# ShieldEsquematico.net
KiCad netlist of a schematic drawn in EAGLE
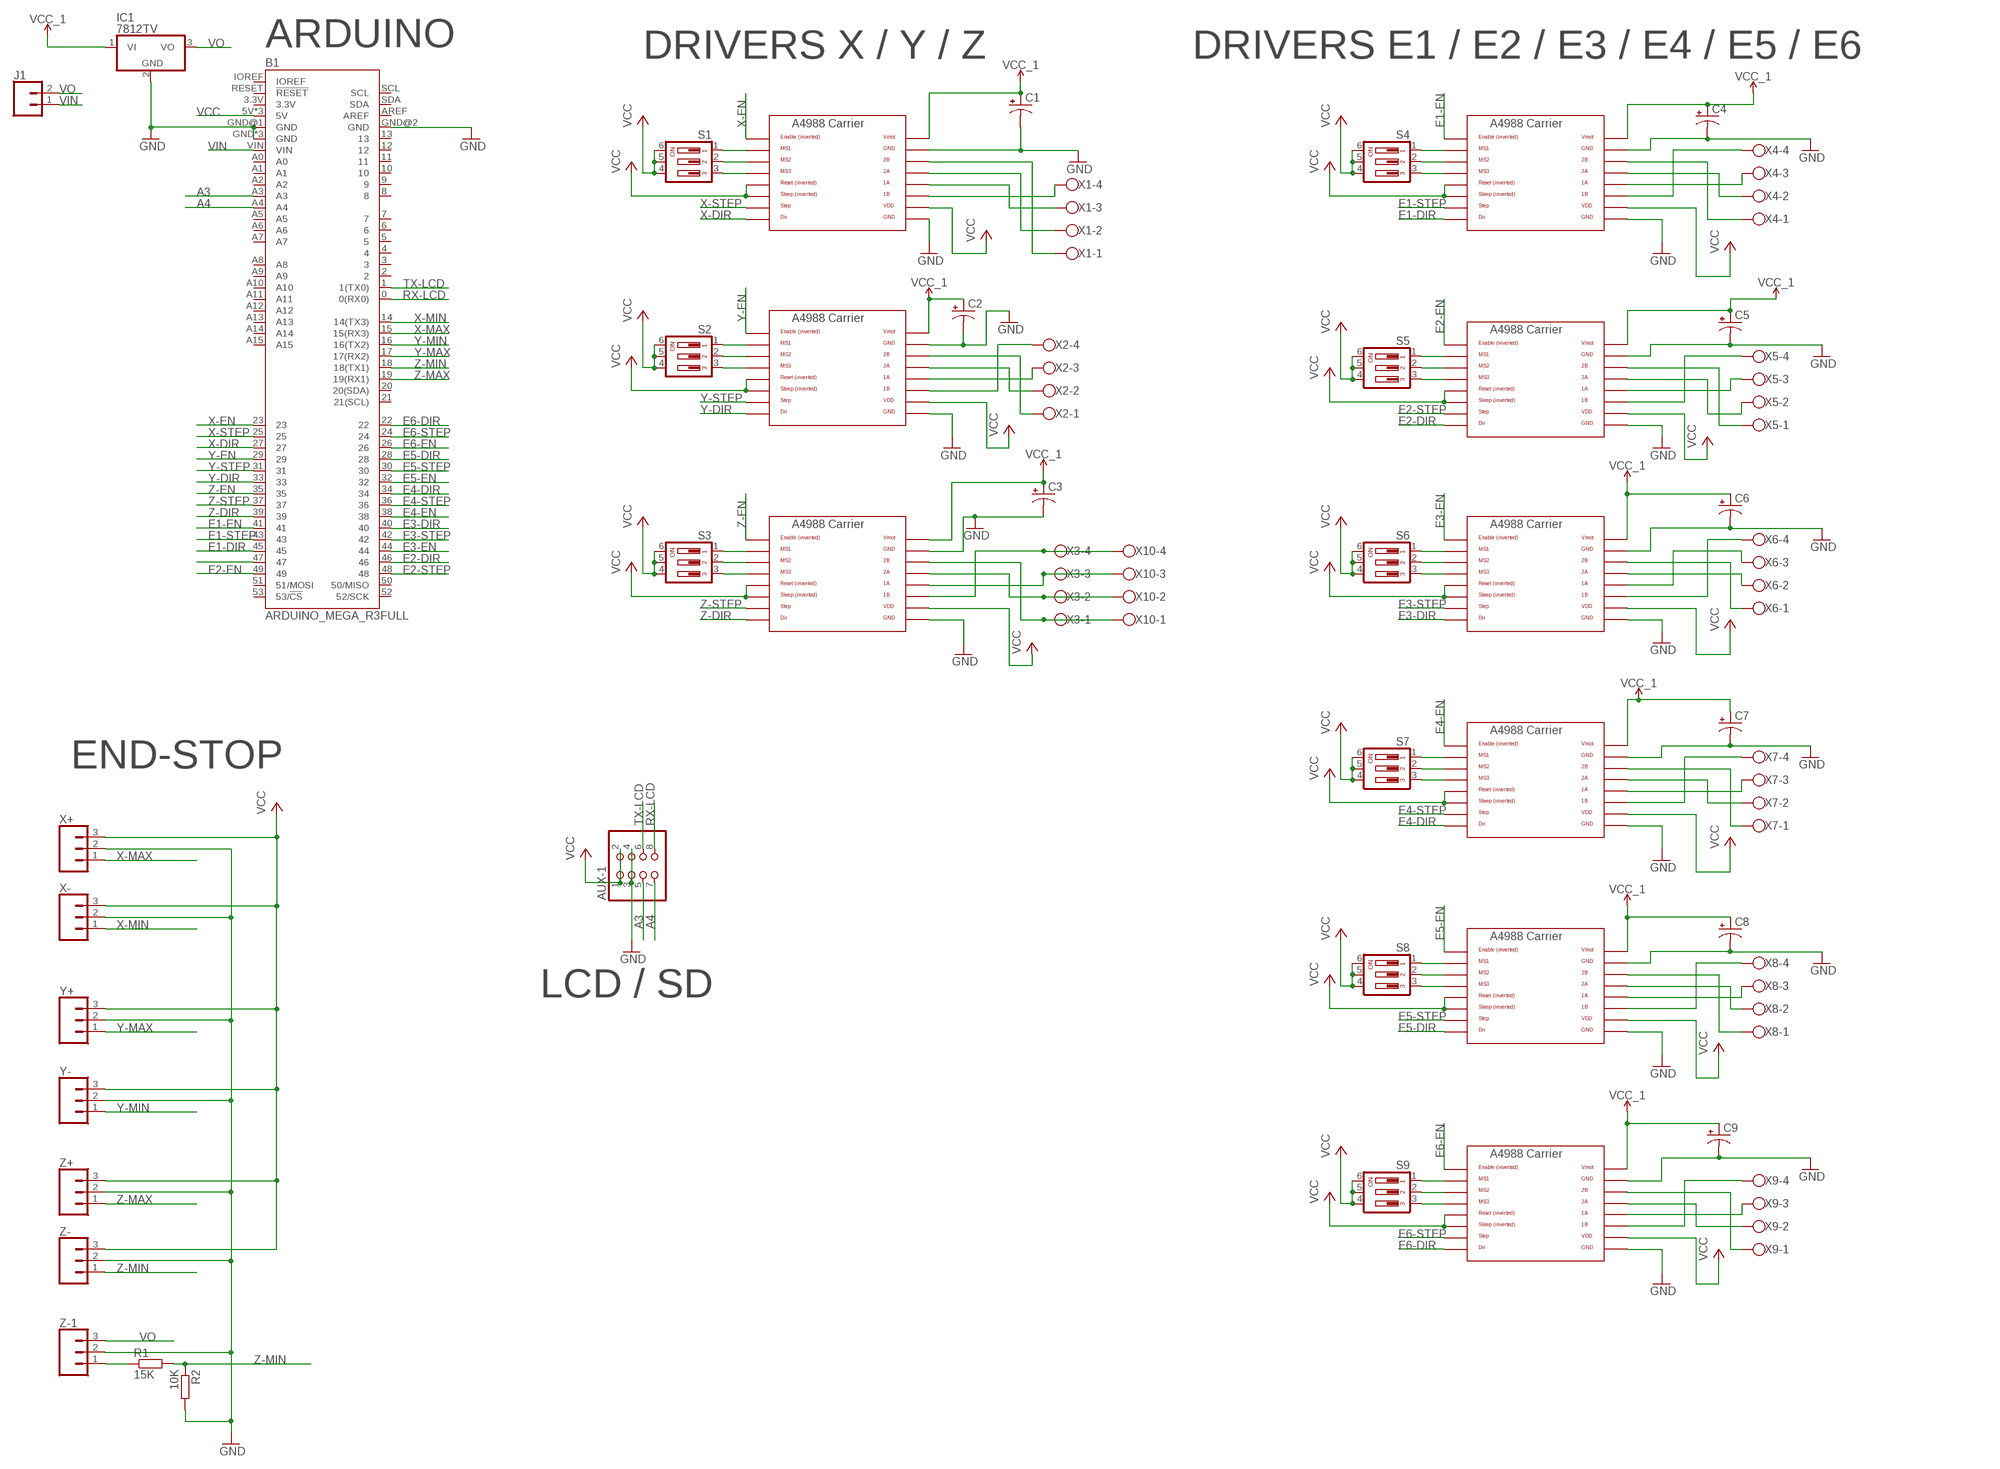
[diagram p0: schematic, sheet 1]

(export (version "E")
  (design (tool "Eeschema 10.0.6"))
  (components
    (comp (ref "AUX-1")
      (value "PINHD-2X4")
      (footprint "eagle-import:2X04")
      (libsource (lib "eagle-import") (part "PINHD-2X4"))
    )
    (comp (ref "B1")
      (value "ARDUINO_MEGA_R3FULL")
      (footprint "eagle-import:ARDUINO_MEGA_NO_SILK")
      (libsource (lib "eagle-import") (part "ARDUINO_MEGA_R3FULL"))
    )
    (comp (ref "C1")
      (value "CPOL-USE5-8.5")
      (footprint "eagle-import:E5-8,5")
      (libsource (lib "eagle-import") (part "CPOL-USE5-8.5"))
    )
    (comp (ref "C2")
      (value "CPOL-USE5-8.5")
      (footprint "eagle-import:E5-8,5")
      (libsource (lib "eagle-import") (part "CPOL-USE5-8.5"))
    )
    (comp (ref "C3")
      (value "CPOL-USE5-8.5")
      (footprint "eagle-import:E5-8,5")
      (libsource (lib "eagle-import") (part "CPOL-USE5-8.5"))
    )
    (comp (ref "C4")
      (value "CPOL-USE5-8.5")
      (footprint "eagle-import:E5-8,5")
      (libsource (lib "eagle-import") (part "CPOL-USE5-8.5"))
    )
    (comp (ref "C5")
      (value "CPOL-USE5-8.5")
      (footprint "eagle-import:E5-8,5")
      (libsource (lib "eagle-import") (part "CPOL-USE5-8.5"))
    )
    (comp (ref "C6")
      (value "CPOL-USE5-8.5")
      (footprint "eagle-import:E5-8,5")
      (libsource (lib "eagle-import") (part "CPOL-USE5-8.5"))
    )
    (comp (ref "C7")
      (value "CPOL-USE5-8.5")
      (footprint "eagle-import:E5-8,5")
      (libsource (lib "eagle-import") (part "CPOL-USE5-8.5"))
    )
    (comp (ref "C8")
      (value "CPOL-USE5-8.5")
      (footprint "eagle-import:E5-8,5")
      (libsource (lib "eagle-import") (part "CPOL-USE5-8.5"))
    )
    (comp (ref "C9")
      (value "CPOL-USE5-8.5")
      (footprint "eagle-import:E5-8,5")
      (libsource (lib "eagle-import") (part "CPOL-USE5-8.5"))
    )
    (comp (ref "IC1")
      (value "7812TV")
      (footprint "eagle-import:TO220V")
      (libsource (lib "eagle-import") (part "78TV12"))
    )
    (comp (ref "J1")
      (value "CONN_02")
      (footprint "eagle-import:1X02")
      (libsource (lib "eagle-import") (part "CONN_02"))
    )
    (comp (ref "R1")
      (value "15K")
      (footprint "eagle-import:0207_10")
      (libsource (lib "eagle-import") (part "R-EU_0207/10"))
    )
    (comp (ref "R2")
      (value "10K")
      (footprint "eagle-import:0207_10")
      (libsource (lib "eagle-import") (part "R-EU_0207/10"))
    )
    (comp (ref "S1")
      (value "DIP03YL")
      (footprint "eagle-import:DIP03YL")
      (libsource (lib "eagle-import") (part "DIP03YL"))
    )
    (comp (ref "S2")
      (value "DIP03YL")
      (footprint "eagle-import:DIP03YL")
      (libsource (lib "eagle-import") (part "DIP03YL"))
    )
    (comp (ref "S3")
      (value "DIP03YL")
      (footprint "eagle-import:DIP03YL")
      (libsource (lib "eagle-import") (part "DIP03YL"))
    )
    (comp (ref "S4")
      (value "DIP03YL")
      (footprint "eagle-import:DIP03YL")
      (libsource (lib "eagle-import") (part "DIP03YL"))
    )
    (comp (ref "S5")
      (value "DIP03YL")
      (footprint "eagle-import:DIP03YL")
      (libsource (lib "eagle-import") (part "DIP03YL"))
    )
    (comp (ref "S6")
      (value "DIP03YL")
      (footprint "eagle-import:DIP03YL")
      (libsource (lib "eagle-import") (part "DIP03YL"))
    )
    (comp (ref "S7")
      (value "DIP03YL")
      (footprint "eagle-import:DIP03YL")
      (libsource (lib "eagle-import") (part "DIP03YL"))
    )
    (comp (ref "S8")
      (value "DIP03YL")
      (footprint "eagle-import:DIP03YL")
      (libsource (lib "eagle-import") (part "DIP03YL"))
    )
    (comp (ref "S9")
      (value "DIP03YL")
      (footprint "eagle-import:DIP03YL")
      (libsource (lib "eagle-import") (part "DIP03YL"))
    )
    (comp (ref "U$1")
      (value "A4988BREAKOUT")
      (footprint "eagle-import:A4988BREAKOUT")
      (libsource (lib "eagle-import") (part "A4988BREAKOUT"))
    )
    (comp (ref "U$2")
      (value "A4988BREAKOUT")
      (footprint "eagle-import:A4988BREAKOUT")
      (libsource (lib "eagle-import") (part "A4988BREAKOUT"))
    )
    (comp (ref "U$3")
      (value "A4988BREAKOUT")
      (footprint "eagle-import:A4988BREAKOUT")
      (libsource (lib "eagle-import") (part "A4988BREAKOUT"))
    )
    (comp (ref "U$4")
      (value "A4988BREAKOUT")
      (footprint "eagle-import:A4988BREAKOUT")
      (libsource (lib "eagle-import") (part "A4988BREAKOUT"))
    )
    (comp (ref "U$5")
      (value "A4988BREAKOUT")
      (footprint "eagle-import:A4988BREAKOUT")
      (libsource (lib "eagle-import") (part "A4988BREAKOUT"))
    )
    (comp (ref "U$6")
      (value "A4988BREAKOUT")
      (footprint "eagle-import:A4988BREAKOUT")
      (libsource (lib "eagle-import") (part "A4988BREAKOUT"))
    )
    (comp (ref "U$7")
      (value "A4988BREAKOUT")
      (footprint "eagle-import:A4988BREAKOUT")
      (libsource (lib "eagle-import") (part "A4988BREAKOUT"))
    )
    (comp (ref "U$8")
      (value "A4988BREAKOUT")
      (footprint "eagle-import:A4988BREAKOUT")
      (libsource (lib "eagle-import") (part "A4988BREAKOUT"))
    )
    (comp (ref "U$9")
      (value "A4988BREAKOUT")
      (footprint "eagle-import:A4988BREAKOUT")
      (libsource (lib "eagle-import") (part "A4988BREAKOUT"))
    )
    (comp (ref "X+")
      (value "CONN_03SCREW_LOCK")
      (footprint "eagle-import:SCREWTERMINAL-3.5MM-3_LOCK.007S")
      (libsource (lib "eagle-import") (part "CONN_03SCREW_LOCK"))
    )
    (comp (ref "X-")
      (value "CONN_03SCREW_LOCK")
      (footprint "eagle-import:SCREWTERMINAL-3.5MM-3_LOCK.007S")
      (libsource (lib "eagle-import") (part "CONN_03SCREW_LOCK"))
    )
    (comp (ref "X1")
      (value "W237-4")
      (footprint "eagle-import:W237-4")
      (libsource (lib "eagle-import") (part "W237-4"))
    )
    (comp (ref "X2")
      (value "W237-4")
      (footprint "eagle-import:W237-4")
      (libsource (lib "eagle-import") (part "W237-4"))
    )
    (comp (ref "X3")
      (value "W237-4")
      (footprint "eagle-import:W237-4")
      (libsource (lib "eagle-import") (part "W237-4"))
    )
    (comp (ref "X4")
      (value "W237-4")
      (footprint "eagle-import:W237-4")
      (libsource (lib "eagle-import") (part "W237-4"))
    )
    (comp (ref "X5")
      (value "W237-4")
      (footprint "eagle-import:W237-4")
      (libsource (lib "eagle-import") (part "W237-4"))
    )
    (comp (ref "X6")
      (value "W237-4")
      (footprint "eagle-import:W237-4")
      (libsource (lib "eagle-import") (part "W237-4"))
    )
    (comp (ref "X7")
      (value "W237-4")
      (footprint "eagle-import:W237-4")
      (libsource (lib "eagle-import") (part "W237-4"))
    )
    (comp (ref "X8")
      (value "W237-4")
      (footprint "eagle-import:W237-4")
      (libsource (lib "eagle-import") (part "W237-4"))
    )
    (comp (ref "X9")
      (value "W237-4")
      (footprint "eagle-import:W237-4")
      (libsource (lib "eagle-import") (part "W237-4"))
    )
    (comp (ref "X10")
      (value "W237-4")
      (footprint "eagle-import:W237-4")
      (libsource (lib "eagle-import") (part "W237-4"))
    )
    (comp (ref "Y+")
      (value "CONN_03SCREW_LOCK")
      (footprint "eagle-import:SCREWTERMINAL-3.5MM-3_LOCK.007S")
      (libsource (lib "eagle-import") (part "CONN_03SCREW_LOCK"))
    )
    (comp (ref "Y-")
      (value "CONN_03SCREW_LOCK")
      (footprint "eagle-import:SCREWTERMINAL-3.5MM-3_LOCK.007S")
      (libsource (lib "eagle-import") (part "CONN_03SCREW_LOCK"))
    )
    (comp (ref "Z+")
      (value "CONN_03SCREW_LOCK")
      (footprint "eagle-import:SCREWTERMINAL-3.5MM-3_LOCK.007S")
      (libsource (lib "eagle-import") (part "CONN_03SCREW_LOCK"))
    )
    (comp (ref "Z-")
      (value "CONN_03SCREW_LOCK")
      (footprint "eagle-import:SCREWTERMINAL-3.5MM-3_LOCK.007S")
      (libsource (lib "eagle-import") (part "CONN_03SCREW_LOCK"))
    )
    (comp (ref "Z-1")
      (value "CONN_03SCREW_LOCK")
      (footprint "eagle-import:SCREWTERMINAL-3.5MM-3_LOCK.007S")
      (libsource (lib "eagle-import") (part "CONN_03SCREW_LOCK"))
    )
  )
  (nets
    (net (code "1") (name "/A3") (class "Default")
      (node (ref "AUX-1") (pin "5") (pinfunction "5_5") (pintype "passive"))
      (node (ref "B1") (pin "A3") (pinfunction "A3_A3") (pintype "bidirectional"))
    )
    (net (code "2") (name "/A4") (class "Default")
      (node (ref "AUX-1") (pin "7") (pinfunction "7_7") (pintype "passive"))
      (node (ref "B1") (pin "A4") (pinfunction "A4_A4") (pintype "bidirectional"))
    )
    (net (code "3") (name "/E1-DIR") (class "Default")
      (node (ref "B1") (pin "45") (pinfunction "45_45") (pintype "bidirectional"))
      (node (ref "U$4") (pin "DIR") (pinfunction "DIR_DIR") (pintype "input"))
    )
    (net (code "4") (name "/E1-EN") (class "Default")
      (node (ref "B1") (pin "41") (pinfunction "41_41") (pintype "bidirectional"))
      (node (ref "U$4") (pin "EN") (pinfunction "EN_EN") (pintype "input"))
    )
    (net (code "5") (name "/E1-STEP") (class "Default")
      (node (ref "B1") (pin "43") (pinfunction "43_43") (pintype "bidirectional"))
      (node (ref "U$4") (pin "STEP") (pinfunction "STEP_STEP") (pintype "input"))
    )
    (net (code "6") (name "/E2-DIR") (class "Default")
      (node (ref "B1") (pin "46") (pinfunction "46_46") (pintype "bidirectional"))
      (node (ref "U$5") (pin "DIR") (pinfunction "DIR_DIR") (pintype "input"))
    )
    (net (code "7") (name "/E2-EN") (class "Default")
      (node (ref "B1") (pin "49") (pinfunction "49_49") (pintype "bidirectional"))
      (node (ref "U$5") (pin "EN") (pinfunction "EN_EN") (pintype "input"))
    )
    (net (code "8") (name "/E2-STEP") (class "Default")
      (node (ref "B1") (pin "48") (pinfunction "48_48") (pintype "bidirectional"))
      (node (ref "U$5") (pin "STEP") (pinfunction "STEP_STEP") (pintype "input"))
    )
    (net (code "9") (name "/E3-DIR") (class "Default")
      (node (ref "B1") (pin "40") (pinfunction "40_40") (pintype "bidirectional"))
      (node (ref "U$6") (pin "DIR") (pinfunction "DIR_DIR") (pintype "input"))
    )
    (net (code "10") (name "/E3-EN") (class "Default")
      (node (ref "B1") (pin "44") (pinfunction "44_44") (pintype "bidirectional"))
      (node (ref "U$6") (pin "EN") (pinfunction "EN_EN") (pintype "input"))
    )
    (net (code "11") (name "/E3-STEP") (class "Default")
      (node (ref "B1") (pin "42") (pinfunction "42_42") (pintype "bidirectional"))
      (node (ref "U$6") (pin "STEP") (pinfunction "STEP_STEP") (pintype "input"))
    )
    (net (code "12") (name "/E4-DIR") (class "Default")
      (node (ref "B1") (pin "34") (pinfunction "34_34") (pintype "bidirectional"))
      (node (ref "U$7") (pin "DIR") (pinfunction "DIR_DIR") (pintype "input"))
    )
    (net (code "13") (name "/E4-EN") (class "Default")
      (node (ref "B1") (pin "38") (pinfunction "38_38") (pintype "bidirectional"))
      (node (ref "U$7") (pin "EN") (pinfunction "EN_EN") (pintype "input"))
    )
    (net (code "14") (name "/E4-STEP") (class "Default")
      (node (ref "B1") (pin "36") (pinfunction "36_36") (pintype "bidirectional"))
      (node (ref "U$7") (pin "STEP") (pinfunction "STEP_STEP") (pintype "input"))
    )
    (net (code "15") (name "/E5-DIR") (class "Default")
      (node (ref "B1") (pin "28") (pinfunction "28_28") (pintype "bidirectional"))
      (node (ref "U$8") (pin "DIR") (pinfunction "DIR_DIR") (pintype "input"))
    )
    (net (code "16") (name "/E5-EN") (class "Default")
      (node (ref "B1") (pin "32") (pinfunction "32_32") (pintype "bidirectional"))
      (node (ref "U$8") (pin "EN") (pinfunction "EN_EN") (pintype "input"))
    )
    (net (code "17") (name "/E5-STEP") (class "Default")
      (node (ref "B1") (pin "30") (pinfunction "30_30") (pintype "bidirectional"))
      (node (ref "U$8") (pin "STEP") (pinfunction "STEP_STEP") (pintype "input"))
    )
    (net (code "18") (name "/E6-DIR") (class "Default")
      (node (ref "B1") (pin "22") (pinfunction "22_22") (pintype "bidirectional"))
      (node (ref "U$9") (pin "DIR") (pinfunction "DIR_DIR") (pintype "input"))
    )
    (net (code "19") (name "/E6-EN") (class "Default")
      (node (ref "B1") (pin "26") (pinfunction "26_26") (pintype "bidirectional"))
      (node (ref "U$9") (pin "EN") (pinfunction "EN_EN") (pintype "input"))
    )
    (net (code "20") (name "/E6-STEP") (class "Default")
      (node (ref "B1") (pin "24") (pinfunction "24_24") (pintype "bidirectional"))
      (node (ref "U$9") (pin "STEP") (pinfunction "STEP_STEP") (pintype "input"))
    )
    (net (code "21") (name "/RX-LCD") (class "Default")
      (node (ref "AUX-1") (pin "8") (pinfunction "8_8") (pintype "passive"))
      (node (ref "B1") (pin "0") (pinfunction "0(RX0)_0") (pintype "bidirectional"))
    )
    (net (code "22") (name "/TX-LCD") (class "Default")
      (node (ref "AUX-1") (pin "6") (pinfunction "6_6") (pintype "passive"))
      (node (ref "B1") (pin "1") (pinfunction "1(TX0)_1") (pintype "bidirectional"))
    )
    (net (code "23") (name "/VIN") (class "Default")
      (node (ref "B1") (pin "VIN") (pinfunction "VIN_VIN") (pintype "bidirectional"))
      (node (ref "J1") (pin "1") (pinfunction "1_1") (pintype "passive"))
    )
    (net (code "24") (name "/VO") (class "Default")
      (node (ref "IC1") (pin "3") (pinfunction "VO_3") (pintype "passive"))
      (node (ref "J1") (pin "2") (pinfunction "2_2") (pintype "passive"))
      (node (ref "Z-1") (pin "3") (pinfunction "3_3") (pintype "passive"))
    )
    (net (code "25") (name "/X-DIR") (class "Default")
      (node (ref "B1") (pin "27") (pinfunction "27_27") (pintype "bidirectional"))
      (node (ref "U$1") (pin "DIR") (pinfunction "DIR_DIR") (pintype "input"))
    )
    (net (code "26") (name "/X-EN") (class "Default")
      (node (ref "B1") (pin "23") (pinfunction "23_23") (pintype "bidirectional"))
      (node (ref "U$1") (pin "EN") (pinfunction "EN_EN") (pintype "input"))
    )
    (net (code "27") (name "/X-MAX") (class "Default")
      (node (ref "B1") (pin "15") (pinfunction "15(RX3)_15") (pintype "bidirectional"))
      (node (ref "X+") (pin "1") (pinfunction "1_1") (pintype "passive"))
    )
    (net (code "28") (name "/X-MIN") (class "Default")
      (node (ref "B1") (pin "14") (pinfunction "14(TX3)_14") (pintype "bidirectional"))
      (node (ref "X-") (pin "1") (pinfunction "1_1") (pintype "passive"))
    )
    (net (code "29") (name "/X-STEP") (class "Default")
      (node (ref "B1") (pin "25") (pinfunction "25_25") (pintype "bidirectional"))
      (node (ref "U$1") (pin "STEP") (pinfunction "STEP_STEP") (pintype "input"))
    )
    (net (code "30") (name "/Y-DIR") (class "Default")
      (node (ref "B1") (pin "33") (pinfunction "33_33") (pintype "bidirectional"))
      (node (ref "U$2") (pin "DIR") (pinfunction "DIR_DIR") (pintype "input"))
    )
    (net (code "31") (name "/Y-EN") (class "Default")
      (node (ref "B1") (pin "29") (pinfunction "29_29") (pintype "bidirectional"))
      (node (ref "U$2") (pin "EN") (pinfunction "EN_EN") (pintype "input"))
    )
    (net (code "32") (name "/Y-MAX") (class "Default")
      (node (ref "B1") (pin "17") (pinfunction "17(RX2)_17") (pintype "bidirectional"))
      (node (ref "Y+") (pin "1") (pinfunction "1_1") (pintype "passive"))
    )
    (net (code "33") (name "/Y-MIN") (class "Default")
      (node (ref "B1") (pin "16") (pinfunction "16(TX2)_16") (pintype "bidirectional"))
      (node (ref "Y-") (pin "1") (pinfunction "1_1") (pintype "passive"))
    )
    (net (code "34") (name "/Y-STEP") (class "Default")
      (node (ref "B1") (pin "31") (pinfunction "31_31") (pintype "bidirectional"))
      (node (ref "U$2") (pin "STEP") (pinfunction "STEP_STEP") (pintype "input"))
    )
    (net (code "35") (name "/Z-DIR") (class "Default")
      (node (ref "B1") (pin "39") (pinfunction "39_39") (pintype "bidirectional"))
      (node (ref "U$3") (pin "DIR") (pinfunction "DIR_DIR") (pintype "input"))
    )
    (net (code "36") (name "/Z-EN") (class "Default")
      (node (ref "B1") (pin "35") (pinfunction "35_35") (pintype "bidirectional"))
      (node (ref "U$3") (pin "EN") (pinfunction "EN_EN") (pintype "input"))
    )
    (net (code "37") (name "/Z-MAX") (class "Default")
      (node (ref "B1") (pin "19") (pinfunction "19(RX1)_19") (pintype "bidirectional"))
      (node (ref "Z+") (pin "1") (pinfunction "1_1") (pintype "passive"))
    )
    (net (code "38") (name "/Z-MIN") (class "Default")
      (node (ref "B1") (pin "18") (pinfunction "18(TX1)_18") (pintype "bidirectional"))
      (node (ref "R1") (pin "2") (pinfunction "2_2") (pintype "passive"))
      (node (ref "R2") (pin "1") (pinfunction "1_1") (pintype "passive"))
      (node (ref "Z-") (pin "1") (pinfunction "1_1") (pintype "passive"))
    )
    (net (code "39") (name "/Z-STEP") (class "Default")
      (node (ref "B1") (pin "37") (pinfunction "37_37") (pintype "bidirectional"))
      (node (ref "U$3") (pin "STEP") (pinfunction "STEP_STEP") (pintype "input"))
    )
    (net (code "40") (name "GND") (class "Default")
      (node (ref "AUX-1") (pin "3") (pinfunction "3_3") (pintype "passive"))
      (node (ref "AUX-1") (pin "4") (pinfunction "4_4") (pintype "passive"))
      (node (ref "B1") (pin "GND") (pinfunction "GND_GND") (pintype "bidirectional"))
      (node (ref "B1") (pin "GND@1") (pinfunction "GND_GND@1") (pintype "bidirectional"))
      (node (ref "B1") (pin "GND@2") (pinfunction "GND_GND@2") (pintype "bidirectional"))
      (node (ref "B1") (pin "GND@3") (pinfunction "GND_GND@3") (pintype "bidirectional"))
      (node (ref "B1") (pin "GND@4") (pinfunction "GND_GND@4") (pintype "bidirectional"))
      (node (ref "C1") (pin "-") (pinfunction "-_-") (pintype "passive"))
      (node (ref "C2") (pin "-") (pinfunction "-_-") (pintype "passive"))
      (node (ref "C3") (pin "-") (pinfunction "-_-") (pintype "passive"))
      (node (ref "C4") (pin "-") (pinfunction "-_-") (pintype "passive"))
      (node (ref "C5") (pin "-") (pinfunction "-_-") (pintype "passive"))
      (node (ref "C6") (pin "-") (pinfunction "-_-") (pintype "passive"))
      (node (ref "C7") (pin "-") (pinfunction "-_-") (pintype "passive"))
      (node (ref "C8") (pin "-") (pinfunction "-_-") (pintype "passive"))
      (node (ref "C9") (pin "-") (pinfunction "-_-") (pintype "passive"))
      (node (ref "IC1") (pin "2") (pinfunction "GND_2") (pintype "passive"))
      (node (ref "R2") (pin "2") (pinfunction "2_2") (pintype "passive"))
      (node (ref "U$1") (pin "GND") (pinfunction "GND_GND") (pintype "power_in"))
      (node (ref "U$1") (pin "GND@0") (pinfunction "GND_GND@0") (pintype "power_in"))
      (node (ref "U$2") (pin "GND") (pinfunction "GND_GND") (pintype "power_in"))
      (node (ref "U$2") (pin "GND@0") (pinfunction "GND_GND@0") (pintype "power_in"))
      (node (ref "U$3") (pin "GND") (pinfunction "GND_GND") (pintype "power_in"))
      (node (ref "U$3") (pin "GND@0") (pinfunction "GND_GND@0") (pintype "power_in"))
      (node (ref "U$4") (pin "GND") (pinfunction "GND_GND") (pintype "power_in"))
      (node (ref "U$4") (pin "GND@0") (pinfunction "GND_GND@0") (pintype "power_in"))
      (node (ref "U$5") (pin "GND") (pinfunction "GND_GND") (pintype "power_in"))
      (node (ref "U$5") (pin "GND@0") (pinfunction "GND_GND@0") (pintype "power_in"))
      (node (ref "U$6") (pin "GND") (pinfunction "GND_GND") (pintype "power_in"))
      (node (ref "U$6") (pin "GND@0") (pinfunction "GND_GND@0") (pintype "power_in"))
      (node (ref "U$7") (pin "GND") (pinfunction "GND_GND") (pintype "power_in"))
      (node (ref "U$7") (pin "GND@0") (pinfunction "GND_GND@0") (pintype "power_in"))
      (node (ref "U$8") (pin "GND") (pinfunction "GND_GND") (pintype "power_in"))
      (node (ref "U$8") (pin "GND@0") (pinfunction "GND_GND@0") (pintype "power_in"))
      (node (ref "U$9") (pin "GND") (pinfunction "GND_GND") (pintype "power_in"))
      (node (ref "U$9") (pin "GND@0") (pinfunction "GND_GND@0") (pintype "power_in"))
      (node (ref "X+") (pin "2") (pinfunction "2_2") (pintype "passive"))
      (node (ref "X-") (pin "2") (pinfunction "2_2") (pintype "passive"))
      (node (ref "Y+") (pin "2") (pinfunction "2_2") (pintype "passive"))
      (node (ref "Y-") (pin "2") (pinfunction "2_2") (pintype "passive"))
      (node (ref "Z+") (pin "2") (pinfunction "2_2") (pintype "passive"))
      (node (ref "Z-") (pin "2") (pinfunction "2_2") (pintype "passive"))
      (node (ref "Z-1") (pin "2") (pinfunction "2_2") (pintype "passive"))
    )
    (net (code "41") (name "Net-(R1-Pad1)") (class "Default")
      (node (ref "R1") (pin "1") (pinfunction "1_1") (pintype "passive"))
      (node (ref "Z-1") (pin "1") (pinfunction "1_1") (pintype "passive"))
    )
    (net (code "42") (name "Net-(S1-Pad1)") (class "Default")
      (node (ref "S1") (pin "1") (pinfunction "1_1") (pintype "passive"))
      (node (ref "U$1") (pin "MS1") (pinfunction "MS1_MS1") (pintype "input"))
    )
    (net (code "43") (name "Net-(S1-Pad2)") (class "Default")
      (node (ref "S1") (pin "2") (pinfunction "2_2") (pintype "passive"))
      (node (ref "U$1") (pin "MS2") (pinfunction "MS2_MS2") (pintype "input"))
    )
    (net (code "44") (name "Net-(S1-Pad3)") (class "Default")
      (node (ref "S1") (pin "3") (pinfunction "3_3") (pintype "passive"))
      (node (ref "U$1") (pin "MS3") (pinfunction "MS3_MS3") (pintype "input"))
    )
    (net (code "45") (name "Net-(S2-Pad1)") (class "Default")
      (node (ref "S2") (pin "1") (pinfunction "1_1") (pintype "passive"))
      (node (ref "U$2") (pin "MS1") (pinfunction "MS1_MS1") (pintype "input"))
    )
    (net (code "46") (name "Net-(S2-Pad2)") (class "Default")
      (node (ref "S2") (pin "2") (pinfunction "2_2") (pintype "passive"))
      (node (ref "U$2") (pin "MS2") (pinfunction "MS2_MS2") (pintype "input"))
    )
    (net (code "47") (name "Net-(S2-Pad3)") (class "Default")
      (node (ref "S2") (pin "3") (pinfunction "3_3") (pintype "passive"))
      (node (ref "U$2") (pin "MS3") (pinfunction "MS3_MS3") (pintype "input"))
    )
    (net (code "48") (name "Net-(S3-Pad1)") (class "Default")
      (node (ref "S3") (pin "1") (pinfunction "1_1") (pintype "passive"))
      (node (ref "U$3") (pin "MS1") (pinfunction "MS1_MS1") (pintype "input"))
    )
    (net (code "49") (name "Net-(S3-Pad2)") (class "Default")
      (node (ref "S3") (pin "2") (pinfunction "2_2") (pintype "passive"))
      (node (ref "U$3") (pin "MS2") (pinfunction "MS2_MS2") (pintype "input"))
    )
    (net (code "50") (name "Net-(S3-Pad3)") (class "Default")
      (node (ref "S3") (pin "3") (pinfunction "3_3") (pintype "passive"))
      (node (ref "U$3") (pin "MS3") (pinfunction "MS3_MS3") (pintype "input"))
    )
    (net (code "51") (name "Net-(S4-Pad1)") (class "Default")
      (node (ref "S4") (pin "1") (pinfunction "1_1") (pintype "passive"))
      (node (ref "U$4") (pin "MS1") (pinfunction "MS1_MS1") (pintype "input"))
    )
    (net (code "52") (name "Net-(S4-Pad2)") (class "Default")
      (node (ref "S4") (pin "2") (pinfunction "2_2") (pintype "passive"))
      (node (ref "U$4") (pin "MS2") (pinfunction "MS2_MS2") (pintype "input"))
    )
    (net (code "53") (name "Net-(S4-Pad3)") (class "Default")
      (node (ref "S4") (pin "3") (pinfunction "3_3") (pintype "passive"))
      (node (ref "U$4") (pin "MS3") (pinfunction "MS3_MS3") (pintype "input"))
    )
    (net (code "54") (name "Net-(S5-Pad1)") (class "Default")
      (node (ref "S5") (pin "1") (pinfunction "1_1") (pintype "passive"))
      (node (ref "U$5") (pin "MS1") (pinfunction "MS1_MS1") (pintype "input"))
    )
    (net (code "55") (name "Net-(S5-Pad2)") (class "Default")
      (node (ref "S5") (pin "2") (pinfunction "2_2") (pintype "passive"))
      (node (ref "U$5") (pin "MS2") (pinfunction "MS2_MS2") (pintype "input"))
    )
    (net (code "56") (name "Net-(S5-Pad3)") (class "Default")
      (node (ref "S5") (pin "3") (pinfunction "3_3") (pintype "passive"))
      (node (ref "U$5") (pin "MS3") (pinfunction "MS3_MS3") (pintype "input"))
    )
    (net (code "57") (name "Net-(S6-Pad1)") (class "Default")
      (node (ref "S6") (pin "1") (pinfunction "1_1") (pintype "passive"))
      (node (ref "U$6") (pin "MS1") (pinfunction "MS1_MS1") (pintype "input"))
    )
    (net (code "58") (name "Net-(S6-Pad2)") (class "Default")
      (node (ref "S6") (pin "2") (pinfunction "2_2") (pintype "passive"))
      (node (ref "U$6") (pin "MS2") (pinfunction "MS2_MS2") (pintype "input"))
    )
    (net (code "59") (name "Net-(S6-Pad3)") (class "Default")
      (node (ref "S6") (pin "3") (pinfunction "3_3") (pintype "passive"))
      (node (ref "U$6") (pin "MS3") (pinfunction "MS3_MS3") (pintype "input"))
    )
    (net (code "60") (name "Net-(S7-Pad1)") (class "Default")
      (node (ref "S7") (pin "1") (pinfunction "1_1") (pintype "passive"))
      (node (ref "U$7") (pin "MS1") (pinfunction "MS1_MS1") (pintype "input"))
    )
    (net (code "61") (name "Net-(S7-Pad2)") (class "Default")
      (node (ref "S7") (pin "2") (pinfunction "2_2") (pintype "passive"))
      (node (ref "U$7") (pin "MS2") (pinfunction "MS2_MS2") (pintype "input"))
    )
    (net (code "62") (name "Net-(S7-Pad3)") (class "Default")
      (node (ref "S7") (pin "3") (pinfunction "3_3") (pintype "passive"))
      (node (ref "U$7") (pin "MS3") (pinfunction "MS3_MS3") (pintype "input"))
    )
    (net (code "63") (name "Net-(S8-Pad1)") (class "Default")
      (node (ref "S8") (pin "1") (pinfunction "1_1") (pintype "passive"))
      (node (ref "U$8") (pin "MS1") (pinfunction "MS1_MS1") (pintype "input"))
    )
    (net (code "64") (name "Net-(S8-Pad2)") (class "Default")
      (node (ref "S8") (pin "2") (pinfunction "2_2") (pintype "passive"))
      (node (ref "U$8") (pin "MS2") (pinfunction "MS2_MS2") (pintype "input"))
    )
    (net (code "65") (name "Net-(S8-Pad3)") (class "Default")
      (node (ref "S8") (pin "3") (pinfunction "3_3") (pintype "passive"))
      (node (ref "U$8") (pin "MS3") (pinfunction "MS3_MS3") (pintype "input"))
    )
    (net (code "66") (name "Net-(S9-Pad1)") (class "Default")
      (node (ref "S9") (pin "1") (pinfunction "1_1") (pintype "passive"))
      (node (ref "U$9") (pin "MS1") (pinfunction "MS1_MS1") (pintype "input"))
    )
    (net (code "67") (name "Net-(S9-Pad2)") (class "Default")
      (node (ref "S9") (pin "2") (pinfunction "2_2") (pintype "passive"))
      (node (ref "U$9") (pin "MS2") (pinfunction "MS2_MS2") (pintype "input"))
    )
    (net (code "68") (name "Net-(S9-Pad3)") (class "Default")
      (node (ref "S9") (pin "3") (pinfunction "3_3") (pintype "passive"))
      (node (ref "U$9") (pin "MS3") (pinfunction "MS3_MS3") (pintype "input"))
    )
    (net (code "69") (name "Net-(X1A-KL)") (class "Default")
      (node (ref "U$1") (pin "2B") (pinfunction "2B_2B") (pintype "output"))
      (node (ref "X1") (pin "1") (pinfunction "KL_1") (pintype "passive"))
    )
    (net (code "70") (name "Net-(X1B-KL)") (class "Default")
      (node (ref "U$1") (pin "2A") (pinfunction "2A_2A") (pintype "output"))
      (node (ref "X1") (pin "2") (pinfunction "KL_2") (pintype "passive"))
    )
    (net (code "71") (name "Net-(X1C-KL)") (class "Default")
      (node (ref "U$1") (pin "1A") (pinfunction "1A_1A") (pintype "output"))
      (node (ref "X1") (pin "3") (pinfunction "KL_3") (pintype "passive"))
    )
    (net (code "72") (name "Net-(X1D-KL)") (class "Default")
      (node (ref "U$1") (pin "1B") (pinfunction "1B_1B") (pintype "output"))
      (node (ref "X1") (pin "4") (pinfunction "KL_4") (pintype "passive"))
    )
    (net (code "73") (name "Net-(X2A-KL)") (class "Default")
      (node (ref "U$2") (pin "2B") (pinfunction "2B_2B") (pintype "output"))
      (node (ref "X2") (pin "1") (pinfunction "KL_1") (pintype "passive"))
    )
    (net (code "74") (name "Net-(X2B-KL)") (class "Default")
      (node (ref "U$2") (pin "2A") (pinfunction "2A_2A") (pintype "output"))
      (node (ref "X2") (pin "2") (pinfunction "KL_2") (pintype "passive"))
    )
    (net (code "75") (name "Net-(X2C-KL)") (class "Default")
      (node (ref "U$2") (pin "1A") (pinfunction "1A_1A") (pintype "output"))
      (node (ref "X2") (pin "3") (pinfunction "KL_3") (pintype "passive"))
    )
    (net (code "76") (name "Net-(X2D-KL)") (class "Default")
      (node (ref "U$2") (pin "1B") (pinfunction "1B_1B") (pintype "output"))
      (node (ref "X2") (pin "4") (pinfunction "KL_4") (pintype "passive"))
    )
    (net (code "77") (name "Net-(X4A-KL)") (class "Default")
      (node (ref "U$4") (pin "2B") (pinfunction "2B_2B") (pintype "output"))
      (node (ref "X4") (pin "1") (pinfunction "KL_1") (pintype "passive"))
    )
    (net (code "78") (name "Net-(X4B-KL)") (class "Default")
      (node (ref "U$4") (pin "2A") (pinfunction "2A_2A") (pintype "output"))
      (node (ref "X4") (pin "2") (pinfunction "KL_2") (pintype "passive"))
    )
    (net (code "79") (name "Net-(X4C-KL)") (class "Default")
      (node (ref "U$4") (pin "1A") (pinfunction "1A_1A") (pintype "output"))
      (node (ref "X4") (pin "3") (pinfunction "KL_3") (pintype "passive"))
    )
    (net (code "80") (name "Net-(X4D-KL)") (class "Default")
      (node (ref "U$4") (pin "1B") (pinfunction "1B_1B") (pintype "output"))
      (node (ref "X4") (pin "4") (pinfunction "KL_4") (pintype "passive"))
    )
    (net (code "81") (name "Net-(X5A-KL)") (class "Default")
      (node (ref "U$5") (pin "2B") (pinfunction "2B_2B") (pintype "output"))
      (node (ref "X5") (pin "1") (pinfunction "KL_1") (pintype "passive"))
    )
    (net (code "82") (name "Net-(X5B-KL)") (class "Default")
      (node (ref "U$5") (pin "2A") (pinfunction "2A_2A") (pintype "output"))
      (node (ref "X5") (pin "2") (pinfunction "KL_2") (pintype "passive"))
    )
    (net (code "83") (name "Net-(X5C-KL)") (class "Default")
      (node (ref "U$5") (pin "1A") (pinfunction "1A_1A") (pintype "output"))
      (node (ref "X5") (pin "3") (pinfunction "KL_3") (pintype "passive"))
    )
    (net (code "84") (name "Net-(X5D-KL)") (class "Default")
      (node (ref "U$5") (pin "1B") (pinfunction "1B_1B") (pintype "output"))
      (node (ref "X5") (pin "4") (pinfunction "KL_4") (pintype "passive"))
    )
    (net (code "85") (name "Net-(X6A-KL)") (class "Default")
      (node (ref "U$6") (pin "2B") (pinfunction "2B_2B") (pintype "output"))
      (node (ref "X6") (pin "1") (pinfunction "KL_1") (pintype "passive"))
    )
    (net (code "86") (name "Net-(X6B-KL)") (class "Default")
      (node (ref "U$6") (pin "2A") (pinfunction "2A_2A") (pintype "output"))
      (node (ref "X6") (pin "2") (pinfunction "KL_2") (pintype "passive"))
    )
    (net (code "87") (name "Net-(X6C-KL)") (class "Default")
      (node (ref "U$6") (pin "1A") (pinfunction "1A_1A") (pintype "output"))
      (node (ref "X6") (pin "3") (pinfunction "KL_3") (pintype "passive"))
    )
    (net (code "88") (name "Net-(X6D-KL)") (class "Default")
      (node (ref "U$6") (pin "1B") (pinfunction "1B_1B") (pintype "output"))
      (node (ref "X6") (pin "4") (pinfunction "KL_4") (pintype "passive"))
    )
    (net (code "89") (name "Net-(X7A-KL)") (class "Default")
      (node (ref "U$7") (pin "2B") (pinfunction "2B_2B") (pintype "output"))
      (node (ref "X7") (pin "1") (pinfunction "KL_1") (pintype "passive"))
    )
    (net (code "90") (name "Net-(X7B-KL)") (class "Default")
      (node (ref "U$7") (pin "2A") (pinfunction "2A_2A") (pintype "output"))
      (node (ref "X7") (pin "2") (pinfunction "KL_2") (pintype "passive"))
    )
    (net (code "91") (name "Net-(X7C-KL)") (class "Default")
      (node (ref "U$7") (pin "1A") (pinfunction "1A_1A") (pintype "output"))
      (node (ref "X7") (pin "3") (pinfunction "KL_3") (pintype "passive"))
    )
    (net (code "92") (name "Net-(X7D-KL)") (class "Default")
      (node (ref "U$7") (pin "1B") (pinfunction "1B_1B") (pintype "output"))
      (node (ref "X7") (pin "4") (pinfunction "KL_4") (pintype "passive"))
    )
    (net (code "93") (name "Net-(X8A-KL)") (class "Default")
      (node (ref "U$8") (pin "2B") (pinfunction "2B_2B") (pintype "output"))
      (node (ref "X8") (pin "1") (pinfunction "KL_1") (pintype "passive"))
    )
    (net (code "94") (name "Net-(X8B-KL)") (class "Default")
      (node (ref "U$8") (pin "2A") (pinfunction "2A_2A") (pintype "output"))
      (node (ref "X8") (pin "2") (pinfunction "KL_2") (pintype "passive"))
    )
    (net (code "95") (name "Net-(X8C-KL)") (class "Default")
      (node (ref "U$8") (pin "1A") (pinfunction "1A_1A") (pintype "output"))
      (node (ref "X8") (pin "3") (pinfunction "KL_3") (pintype "passive"))
    )
    (net (code "96") (name "Net-(X8D-KL)") (class "Default")
      (node (ref "U$8") (pin "1B") (pinfunction "1B_1B") (pintype "output"))
      (node (ref "X8") (pin "4") (pinfunction "KL_4") (pintype "passive"))
    )
    (net (code "97") (name "Net-(X9A-KL)") (class "Default")
      (node (ref "U$9") (pin "2B") (pinfunction "2B_2B") (pintype "output"))
      (node (ref "X9") (pin "1") (pinfunction "KL_1") (pintype "passive"))
    )
    (net (code "98") (name "Net-(X9B-KL)") (class "Default")
      (node (ref "U$9") (pin "2A") (pinfunction "2A_2A") (pintype "output"))
      (node (ref "X9") (pin "2") (pinfunction "KL_2") (pintype "passive"))
    )
    (net (code "99") (name "Net-(X9C-KL)") (class "Default")
      (node (ref "U$9") (pin "1A") (pinfunction "1A_1A") (pintype "output"))
      (node (ref "X9") (pin "3") (pinfunction "KL_3") (pintype "passive"))
    )
    (net (code "100") (name "Net-(X9D-KL)") (class "Default")
      (node (ref "U$9") (pin "1B") (pinfunction "1B_1B") (pintype "output"))
      (node (ref "X9") (pin "4") (pinfunction "KL_4") (pintype "passive"))
    )
    (net (code "101") (name "Net-(X10A-KL)") (class "Default")
      (node (ref "U$3") (pin "2B") (pinfunction "2B_2B") (pintype "output"))
      (node (ref "X10") (pin "1") (pinfunction "KL_1") (pintype "passive"))
      (node (ref "X3") (pin "1") (pinfunction "KL_1") (pintype "passive"))
    )
    (net (code "102") (name "Net-(X10B-KL)") (class "Default")
      (node (ref "U$3") (pin "2A") (pinfunction "2A_2A") (pintype "output"))
      (node (ref "X10") (pin "2") (pinfunction "KL_2") (pintype "passive"))
      (node (ref "X3") (pin "2") (pinfunction "KL_2") (pintype "passive"))
    )
    (net (code "103") (name "Net-(X10C-KL)") (class "Default")
      (node (ref "U$3") (pin "1A") (pinfunction "1A_1A") (pintype "output"))
      (node (ref "X10") (pin "3") (pinfunction "KL_3") (pintype "passive"))
      (node (ref "X3") (pin "3") (pinfunction "KL_3") (pintype "passive"))
    )
    (net (code "104") (name "Net-(X10D-KL)") (class "Default")
      (node (ref "U$3") (pin "1B") (pinfunction "1B_1B") (pintype "output"))
      (node (ref "X10") (pin "4") (pinfunction "KL_4") (pintype "passive"))
      (node (ref "X3") (pin "4") (pinfunction "KL_4") (pintype "passive"))
    )
    (net (code "105") (name "VCC") (class "Default")
      (node (ref "AUX-1") (pin "1") (pinfunction "1_1") (pintype "passive"))
      (node (ref "AUX-1") (pin "2") (pinfunction "2_2") (pintype "passive"))
      (node (ref "B1") (pin "5V") (pinfunction "5V_5V") (pintype "bidirectional"))
      (node (ref "B1") (pin "5V@1") (pinfunction "5V_5V@1") (pintype "bidirectional"))
      (node (ref "B1") (pin "5V@2") (pinfunction "5V_5V@2") (pintype "bidirectional"))
      (node (ref "S1") (pin "4") (pinfunction "4_4") (pintype "passive"))
      (node (ref "S1") (pin "5") (pinfunction "5_5") (pintype "passive"))
      (node (ref "S1") (pin "6") (pinfunction "6_6") (pintype "passive"))
      (node (ref "S2") (pin "4") (pinfunction "4_4") (pintype "passive"))
      (node (ref "S2") (pin "5") (pinfunction "5_5") (pintype "passive"))
      (node (ref "S2") (pin "6") (pinfunction "6_6") (pintype "passive"))
      (node (ref "S3") (pin "4") (pinfunction "4_4") (pintype "passive"))
      (node (ref "S3") (pin "5") (pinfunction "5_5") (pintype "passive"))
      (node (ref "S3") (pin "6") (pinfunction "6_6") (pintype "passive"))
      (node (ref "S4") (pin "4") (pinfunction "4_4") (pintype "passive"))
      (node (ref "S4") (pin "5") (pinfunction "5_5") (pintype "passive"))
      (node (ref "S4") (pin "6") (pinfunction "6_6") (pintype "passive"))
      (node (ref "S5") (pin "4") (pinfunction "4_4") (pintype "passive"))
      (node (ref "S5") (pin "5") (pinfunction "5_5") (pintype "passive"))
      (node (ref "S5") (pin "6") (pinfunction "6_6") (pintype "passive"))
      (node (ref "S6") (pin "4") (pinfunction "4_4") (pintype "passive"))
      (node (ref "S6") (pin "5") (pinfunction "5_5") (pintype "passive"))
      (node (ref "S6") (pin "6") (pinfunction "6_6") (pintype "passive"))
      (node (ref "S7") (pin "4") (pinfunction "4_4") (pintype "passive"))
      (node (ref "S7") (pin "5") (pinfunction "5_5") (pintype "passive"))
      (node (ref "S7") (pin "6") (pinfunction "6_6") (pintype "passive"))
      (node (ref "S8") (pin "4") (pinfunction "4_4") (pintype "passive"))
      (node (ref "S8") (pin "5") (pinfunction "5_5") (pintype "passive"))
      (node (ref "S8") (pin "6") (pinfunction "6_6") (pintype "passive"))
      (node (ref "S9") (pin "4") (pinfunction "4_4") (pintype "passive"))
      (node (ref "S9") (pin "5") (pinfunction "5_5") (pintype "passive"))
      (node (ref "S9") (pin "6") (pinfunction "6_6") (pintype "passive"))
      (node (ref "U$1") (pin "RST") (pinfunction "RST_RST") (pintype "input"))
      (node (ref "U$1") (pin "SLP") (pinfunction "SLEEP_SLP") (pintype "input"))
      (node (ref "U$1") (pin "VDD") (pinfunction "VDD_VDD") (pintype "power_in"))
      (node (ref "U$2") (pin "RST") (pinfunction "RST_RST") (pintype "input"))
      (node (ref "U$2") (pin "SLP") (pinfunction "SLEEP_SLP") (pintype "input"))
      (node (ref "U$2") (pin "VDD") (pinfunction "VDD_VDD") (pintype "power_in"))
      (node (ref "U$3") (pin "RST") (pinfunction "RST_RST") (pintype "input"))
      (node (ref "U$3") (pin "SLP") (pinfunction "SLEEP_SLP") (pintype "input"))
      (node (ref "U$3") (pin "VDD") (pinfunction "VDD_VDD") (pintype "power_in"))
      (node (ref "U$4") (pin "RST") (pinfunction "RST_RST") (pintype "input"))
      (node (ref "U$4") (pin "SLP") (pinfunction "SLEEP_SLP") (pintype "input"))
      (node (ref "U$4") (pin "VDD") (pinfunction "VDD_VDD") (pintype "power_in"))
      (node (ref "U$5") (pin "RST") (pinfunction "RST_RST") (pintype "input"))
      (node (ref "U$5") (pin "SLP") (pinfunction "SLEEP_SLP") (pintype "input"))
      (node (ref "U$5") (pin "VDD") (pinfunction "VDD_VDD") (pintype "power_in"))
      (node (ref "U$6") (pin "RST") (pinfunction "RST_RST") (pintype "input"))
      (node (ref "U$6") (pin "SLP") (pinfunction "SLEEP_SLP") (pintype "input"))
      (node (ref "U$6") (pin "VDD") (pinfunction "VDD_VDD") (pintype "power_in"))
      (node (ref "U$7") (pin "RST") (pinfunction "RST_RST") (pintype "input"))
      (node (ref "U$7") (pin "SLP") (pinfunction "SLEEP_SLP") (pintype "input"))
      (node (ref "U$7") (pin "VDD") (pinfunction "VDD_VDD") (pintype "power_in"))
      (node (ref "U$8") (pin "RST") (pinfunction "RST_RST") (pintype "input"))
      (node (ref "U$8") (pin "SLP") (pinfunction "SLEEP_SLP") (pintype "input"))
      (node (ref "U$8") (pin "VDD") (pinfunction "VDD_VDD") (pintype "power_in"))
      (node (ref "U$9") (pin "RST") (pinfunction "RST_RST") (pintype "input"))
      (node (ref "U$9") (pin "SLP") (pinfunction "SLEEP_SLP") (pintype "input"))
      (node (ref "U$9") (pin "VDD") (pinfunction "VDD_VDD") (pintype "power_in"))
      (node (ref "X+") (pin "3") (pinfunction "3_3") (pintype "passive"))
      (node (ref "X-") (pin "3") (pinfunction "3_3") (pintype "passive"))
      (node (ref "Y+") (pin "3") (pinfunction "3_3") (pintype "passive"))
      (node (ref "Y-") (pin "3") (pinfunction "3_3") (pintype "passive"))
      (node (ref "Z+") (pin "3") (pinfunction "3_3") (pintype "passive"))
      (node (ref "Z-") (pin "3") (pinfunction "3_3") (pintype "passive"))
    )
    (net (code "106") (name "VCC_1") (class "Default")
      (node (ref "C1") (pin "+") (pinfunction "+_+") (pintype "passive"))
      (node (ref "C2") (pin "+") (pinfunction "+_+") (pintype "passive"))
      (node (ref "C3") (pin "+") (pinfunction "+_+") (pintype "passive"))
      (node (ref "C4") (pin "+") (pinfunction "+_+") (pintype "passive"))
      (node (ref "C5") (pin "+") (pinfunction "+_+") (pintype "passive"))
      (node (ref "C6") (pin "+") (pinfunction "+_+") (pintype "passive"))
      (node (ref "C7") (pin "+") (pinfunction "+_+") (pintype "passive"))
      (node (ref "C8") (pin "+") (pinfunction "+_+") (pintype "passive"))
      (node (ref "C9") (pin "+") (pinfunction "+_+") (pintype "passive"))
      (node (ref "IC1") (pin "1") (pinfunction "VI_1") (pintype "input"))
      (node (ref "U$1") (pin "VMOT") (pinfunction "VMOT_VMOT") (pintype "power_in"))
      (node (ref "U$2") (pin "VMOT") (pinfunction "VMOT_VMOT") (pintype "power_in"))
      (node (ref "U$3") (pin "VMOT") (pinfunction "VMOT_VMOT") (pintype "power_in"))
      (node (ref "U$4") (pin "VMOT") (pinfunction "VMOT_VMOT") (pintype "power_in"))
      (node (ref "U$5") (pin "VMOT") (pinfunction "VMOT_VMOT") (pintype "power_in"))
      (node (ref "U$6") (pin "VMOT") (pinfunction "VMOT_VMOT") (pintype "power_in"))
      (node (ref "U$7") (pin "VMOT") (pinfunction "VMOT_VMOT") (pintype "power_in"))
      (node (ref "U$8") (pin "VMOT") (pinfunction "VMOT_VMOT") (pintype "power_in"))
      (node (ref "U$9") (pin "VMOT") (pinfunction "VMOT_VMOT") (pintype "power_in"))
    )
    (net (code "107") (name "unconnected-(B1-20(SDA)-Pad20)") (class "Default")
      (node (ref "B1") (pin "20") (pinfunction "20(SDA)_20") (pintype "bidirectional"))
    )
    (net (code "108") (name "unconnected-(B1-21(SCL)-Pad21)") (class "Default")
      (node (ref "B1") (pin "21") (pinfunction "21(SCL)_21") (pintype "bidirectional"))
    )
    (net (code "109") (name "unconnected-(B1-50{slash}MISO-Pad50)") (class "Default")
      (node (ref "B1") (pin "50") (pinfunction "50/MISO_50") (pintype "bidirectional"))
    )
    (net (code "110") (name "unconnected-(B1-51{slash}MOSI-Pad51)") (class "Default")
      (node (ref "B1") (pin "51") (pinfunction "51/MOSI_51") (pintype "bidirectional"))
    )
    (net (code "111") (name "unconnected-(B1-52{slash}SCK-Pad52)") (class "Default")
      (node (ref "B1") (pin "52") (pinfunction "52/SCK_52") (pintype "bidirectional"))
    )
    (net (code "112") (name "unconnected-(B1-53{slash}~{CS}-Pad53)") (class "Default")
      (node (ref "B1") (pin "53") (pinfunction "53/~{CS}_53") (pintype "bidirectional"))
    )
    (net (code "113") (name "unconnected-(B1-Pad2)") (class "Default")
      (node (ref "B1") (pin "2") (pinfunction "2_2") (pintype "bidirectional"))
    )
    (net (code "114") (name "unconnected-(B1-Pad3)") (class "Default")
      (node (ref "B1") (pin "3") (pinfunction "3_3") (pintype "bidirectional"))
    )
    (net (code "115") (name "unconnected-(B1-Pad3.3V)") (class "Default")
      (node (ref "B1") (pin "3.3V") (pinfunction "3.3V_3.3V") (pintype "bidirectional"))
    )
    (net (code "116") (name "unconnected-(B1-Pad4)") (class "Default")
      (node (ref "B1") (pin "4") (pinfunction "4_4") (pintype "bidirectional"))
    )
    (net (code "117") (name "unconnected-(B1-Pad5)") (class "Default")
      (node (ref "B1") (pin "5") (pinfunction "5_5") (pintype "bidirectional"))
    )
    (net (code "118") (name "unconnected-(B1-Pad6)") (class "Default")
      (node (ref "B1") (pin "6") (pinfunction "6_6") (pintype "bidirectional"))
    )
    (net (code "119") (name "unconnected-(B1-Pad7)") (class "Default")
      (node (ref "B1") (pin "7") (pinfunction "7_7") (pintype "bidirectional"))
    )
    (net (code "120") (name "unconnected-(B1-Pad8)") (class "Default")
      (node (ref "B1") (pin "8") (pinfunction "8_8") (pintype "bidirectional"))
    )
    (net (code "121") (name "unconnected-(B1-Pad9)") (class "Default")
      (node (ref "B1") (pin "9") (pinfunction "9_9") (pintype "bidirectional"))
    )
    (net (code "122") (name "unconnected-(B1-Pad10)") (class "Default")
      (node (ref "B1") (pin "10") (pinfunction "10_10") (pintype "bidirectional"))
    )
    (net (code "123") (name "unconnected-(B1-Pad11)") (class "Default")
      (node (ref "B1") (pin "11") (pinfunction "11_11") (pintype "bidirectional"))
    )
    (net (code "124") (name "unconnected-(B1-Pad12)") (class "Default")
      (node (ref "B1") (pin "12") (pinfunction "12_12") (pintype "bidirectional"))
    )
    (net (code "125") (name "unconnected-(B1-Pad13)") (class "Default")
      (node (ref "B1") (pin "13") (pinfunction "13_13") (pintype "bidirectional"))
    )
    (net (code "126") (name "unconnected-(B1-Pad47)") (class "Default")
      (node (ref "B1") (pin "47") (pinfunction "47_47") (pintype "bidirectional"))
    )
    (net (code "127") (name "unconnected-(B1-PadA0)") (class "Default")
      (node (ref "B1") (pin "A0") (pinfunction "A0_A0") (pintype "bidirectional"))
    )
    (net (code "128") (name "unconnected-(B1-PadA1)") (class "Default")
      (node (ref "B1") (pin "A1") (pinfunction "A1_A1") (pintype "bidirectional"))
    )
    (net (code "129") (name "unconnected-(B1-PadA2)") (class "Default")
      (node (ref "B1") (pin "A2") (pinfunction "A2_A2") (pintype "bidirectional"))
    )
    (net (code "130") (name "unconnected-(B1-PadA5)") (class "Default")
      (node (ref "B1") (pin "A5") (pinfunction "A5_A5") (pintype "bidirectional"))
    )
    (net (code "131") (name "unconnected-(B1-PadA6)") (class "Default")
      (node (ref "B1") (pin "A6") (pinfunction "A6_A6") (pintype "bidirectional"))
    )
    (net (code "132") (name "unconnected-(B1-PadA7)") (class "Default")
      (node (ref "B1") (pin "A7") (pinfunction "A7_A7") (pintype "bidirectional"))
    )
    (net (code "133") (name "unconnected-(B1-PadA8)") (class "Default")
      (node (ref "B1") (pin "A8") (pinfunction "A8_A8") (pintype "bidirectional"))
    )
    (net (code "134") (name "unconnected-(B1-PadA9)") (class "Default")
      (node (ref "B1") (pin "A9") (pinfunction "A9_A9") (pintype "bidirectional"))
    )
    (net (code "135") (name "unconnected-(B1-PadA10)") (class "Default")
      (node (ref "B1") (pin "A10") (pinfunction "A10_A10") (pintype "bidirectional"))
    )
    (net (code "136") (name "unconnected-(B1-PadA11)") (class "Default")
      (node (ref "B1") (pin "A11") (pinfunction "A11_A11") (pintype "bidirectional"))
    )
    (net (code "137") (name "unconnected-(B1-PadA12)") (class "Default")
      (node (ref "B1") (pin "A12") (pinfunction "A12_A12") (pintype "bidirectional"))
    )
    (net (code "138") (name "unconnected-(B1-PadA13)") (class "Default")
      (node (ref "B1") (pin "A13") (pinfunction "A13_A13") (pintype "bidirectional"))
    )
    (net (code "139") (name "unconnected-(B1-PadA14)") (class "Default")
      (node (ref "B1") (pin "A14") (pinfunction "A14_A14") (pintype "bidirectional"))
    )
    (net (code "140") (name "unconnected-(B1-PadA15)") (class "Default")
      (node (ref "B1") (pin "A15") (pinfunction "A15_A15") (pintype "bidirectional"))
    )
    (net (code "141") (name "unconnected-(B1-PadAREF)") (class "Default")
      (node (ref "B1") (pin "AREF") (pinfunction "AREF_AREF") (pintype "bidirectional"))
    )
    (net (code "142") (name "unconnected-(B1-PadIOREF)") (class "Default")
      (node (ref "B1") (pin "IOREF") (pinfunction "IOREF_IOREF") (pintype "bidirectional"))
    )
    (net (code "143") (name "unconnected-(B1-PadSCL)") (class "Default")
      (node (ref "B1") (pin "SCL") (pinfunction "SCL_SCL") (pintype "bidirectional"))
    )
    (net (code "144") (name "unconnected-(B1-PadSDA)") (class "Default")
      (node (ref "B1") (pin "SDA") (pinfunction "SDA_SDA") (pintype "bidirectional"))
    )
    (net (code "145") (name "unconnected-(B1-~{RESET}-PadRESET)") (class "Default")
      (node (ref "B1") (pin "RESET") (pinfunction "~{RESET}_RESET") (pintype "bidirectional"))
    )
  )
)
